# Backpanel.net
KiCad netlist of a schematic drawn in Altium Designer
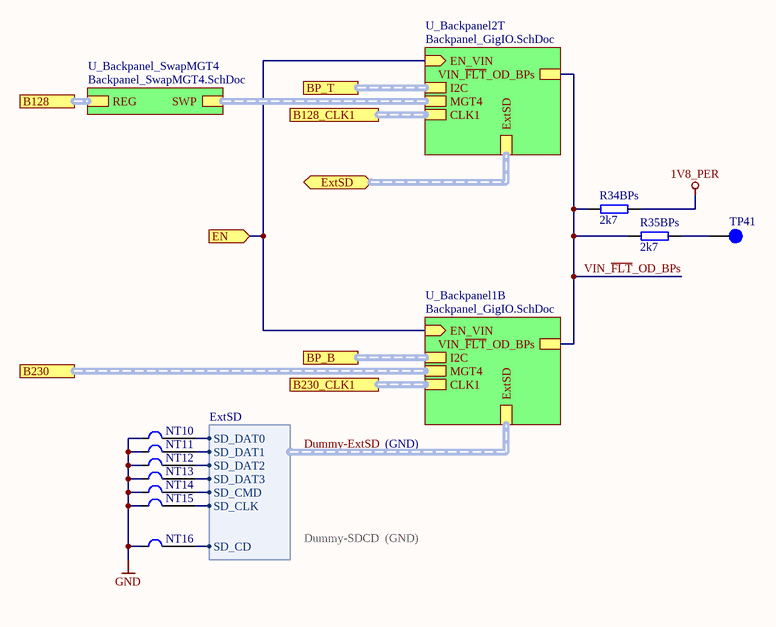
[diagram p0: Backpanel.SchDoc]

(export (version "E")
  (design (tool "Eeschema 10.0.6"))
  (components
    (comp (ref "NT10")
      (value "Net Tie 1 to 1")
      (footprint "1_to_1_NetTie_0.1mm")
      (description "Net Tie 1 to 1. Joins two nets without producing a DRC error or renaming one of the nets")
      (fields (field (name "CREATED BY") "MGeier"))
      (libsource (lib "user") (part "NetTie_1_to_1_small"))
    )
    (comp (ref "NT11")
      (value "Net Tie 1 to 1")
      (footprint "1_to_1_NetTie_0.1mm")
      (description "Net Tie 1 to 1. Joins two nets without producing a DRC error or renaming one of the nets")
      (fields (field (name "CREATED BY") "MGeier"))
      (libsource (lib "user") (part "NetTie_1_to_1_small"))
    )
    (comp (ref "NT12")
      (value "Net Tie 1 to 1")
      (footprint "1_to_1_NetTie_0.1mm")
      (description "Net Tie 1 to 1. Joins two nets without producing a DRC error or renaming one of the nets")
      (fields (field (name "CREATED BY") "MGeier"))
      (libsource (lib "user") (part "NetTie_1_to_1_small"))
    )
    (comp (ref "NT13")
      (value "Net Tie 1 to 1")
      (footprint "1_to_1_NetTie_0.1mm")
      (description "Net Tie 1 to 1. Joins two nets without producing a DRC error or renaming one of the nets")
      (fields (field (name "CREATED BY") "MGeier"))
      (libsource (lib "user") (part "NetTie_1_to_1_small"))
    )
    (comp (ref "NT14")
      (value "Net Tie 1 to 1")
      (footprint "1_to_1_NetTie_0.1mm")
      (description "Net Tie 1 to 1. Joins two nets without producing a DRC error or renaming one of the nets")
      (fields (field (name "CREATED BY") "MGeier"))
      (libsource (lib "user") (part "NetTie_1_to_1_small"))
    )
    (comp (ref "NT15")
      (value "Net Tie 1 to 1")
      (footprint "1_to_1_NetTie_0.1mm")
      (description "Net Tie 1 to 1. Joins two nets without producing a DRC error or renaming one of the nets")
      (fields (field (name "CREATED BY") "MGeier"))
      (libsource (lib "user") (part "NetTie_1_to_1_small"))
    )
    (comp (ref "NT16")
      (value "Net Tie 1 to 1")
      (footprint "1_to_1_NetTie_0.1mm")
      (description "Net Tie 1 to 1. Joins two nets without producing a DRC error or renaming one of the nets")
      (fields (field (name "CREATED BY") "MGeier"))
      (libsource (lib "user") (part "NetTie_1_to_1_small"))
    )
    (comp (ref "R34BPs")
      (value "2k7")
      (footprint "R_0603_TE")
      (description "Generic resistor")
      (fields
        (field (name "MANUFACTURER PART NUMBER") "UZgen_R_0603_2k7")
        (field (name "MANUFACTURER") "UZgen")
        (field (name "CREATED FROM") "UZgenTool")
      )
      (libsource (lib "user") (part "RES"))
    )
    (comp (ref "R35BPs")
      (value "2k7")
      (footprint "R_0603_TE")
      (description "Generic resistor")
      (fields
        (field (name "MANUFACTURER PART NUMBER") "UZgen_R_0603_2k7")
        (field (name "MANUFACTURER") "UZgen")
        (field (name "CREATED FROM") "UZgenTool")
      )
      (libsource (lib "user") (part "RES"))
    )
    (comp (ref "TP41")
      (value "Testpoint 1mm")
      (footprint "TP_1mm")
      (fields
        (field (name "MANUFACTURER PART NUMBER") "NULL")
        (field (name "CREATED") "2018_06_25_AGeiger")
        (field (name "CREATED FROM") "AGeiger")
      )
      (libsource (lib "user") (part "TP_1mm"))
    )
  )
  (nets
    (net (code "19") (name "/SD_CD") (class "Default")
      (node (ref "NT16") (pin "2") (pinfunction "2_2") (pintype "passive"))
    )
    (net (code "20") (name "/SD_CLK") (class "Default")
      (node (ref "NT15") (pin "2") (pinfunction "2_2") (pintype "passive"))
    )
    (net (code "21") (name "/SD_CMD") (class "Default")
      (node (ref "NT14") (pin "2") (pinfunction "2_2") (pintype "passive"))
    )
    (net (code "22") (name "/SD_DAT0") (class "Default")
      (node (ref "NT10") (pin "2") (pinfunction "2_2") (pintype "passive"))
    )
    (net (code "23") (name "/SD_DAT1") (class "Default")
      (node (ref "NT11") (pin "2") (pinfunction "2_2") (pintype "passive"))
    )
    (net (code "24") (name "/SD_DAT2") (class "Default")
      (node (ref "NT12") (pin "2") (pinfunction "2_2") (pintype "passive"))
    )
    (net (code "25") (name "/SD_DAT3") (class "Default")
      (node (ref "NT13") (pin "2") (pinfunction "2_2") (pintype "passive"))
    )
    (net (code "26") (name "/VIN_~{FLT}_OD_BPs") (class "Default")
      (node (ref "R34BPs") (pin "1") (pinfunction "1_1") (pintype "passive"))
      (node (ref "R35BPs") (pin "1") (pinfunction "1_1") (pintype "passive"))
    )
    (net (code "27") (name "1V8_PER") (class "Default")
      (node (ref "R34BPs") (pin "2") (pinfunction "2_2") (pintype "passive"))
    )
    (net (code "28") (name "GND") (class "Default")
      (node (ref "NT10") (pin "1") (pinfunction "1_1") (pintype "passive"))
      (node (ref "NT11") (pin "1") (pinfunction "1_1") (pintype "passive"))
      (node (ref "NT12") (pin "1") (pinfunction "1_1") (pintype "passive"))
      (node (ref "NT13") (pin "1") (pinfunction "1_1") (pintype "passive"))
      (node (ref "NT14") (pin "1") (pinfunction "1_1") (pintype "passive"))
      (node (ref "NT15") (pin "1") (pinfunction "1_1") (pintype "passive"))
      (node (ref "NT16") (pin "1") (pinfunction "1_1") (pintype "passive"))
    )
    (net (code "29") (name "Net-(R35BPs-Pad2)") (class "Default")
      (node (ref "R35BPs") (pin "2") (pinfunction "2_2") (pintype "passive"))
      (node (ref "TP41") (pin "1") (pintype "passive"))
    )
  )
)
